# SHT31_Breakout_v1.net
KiCad netlist of a schematic drawn in EAGLE
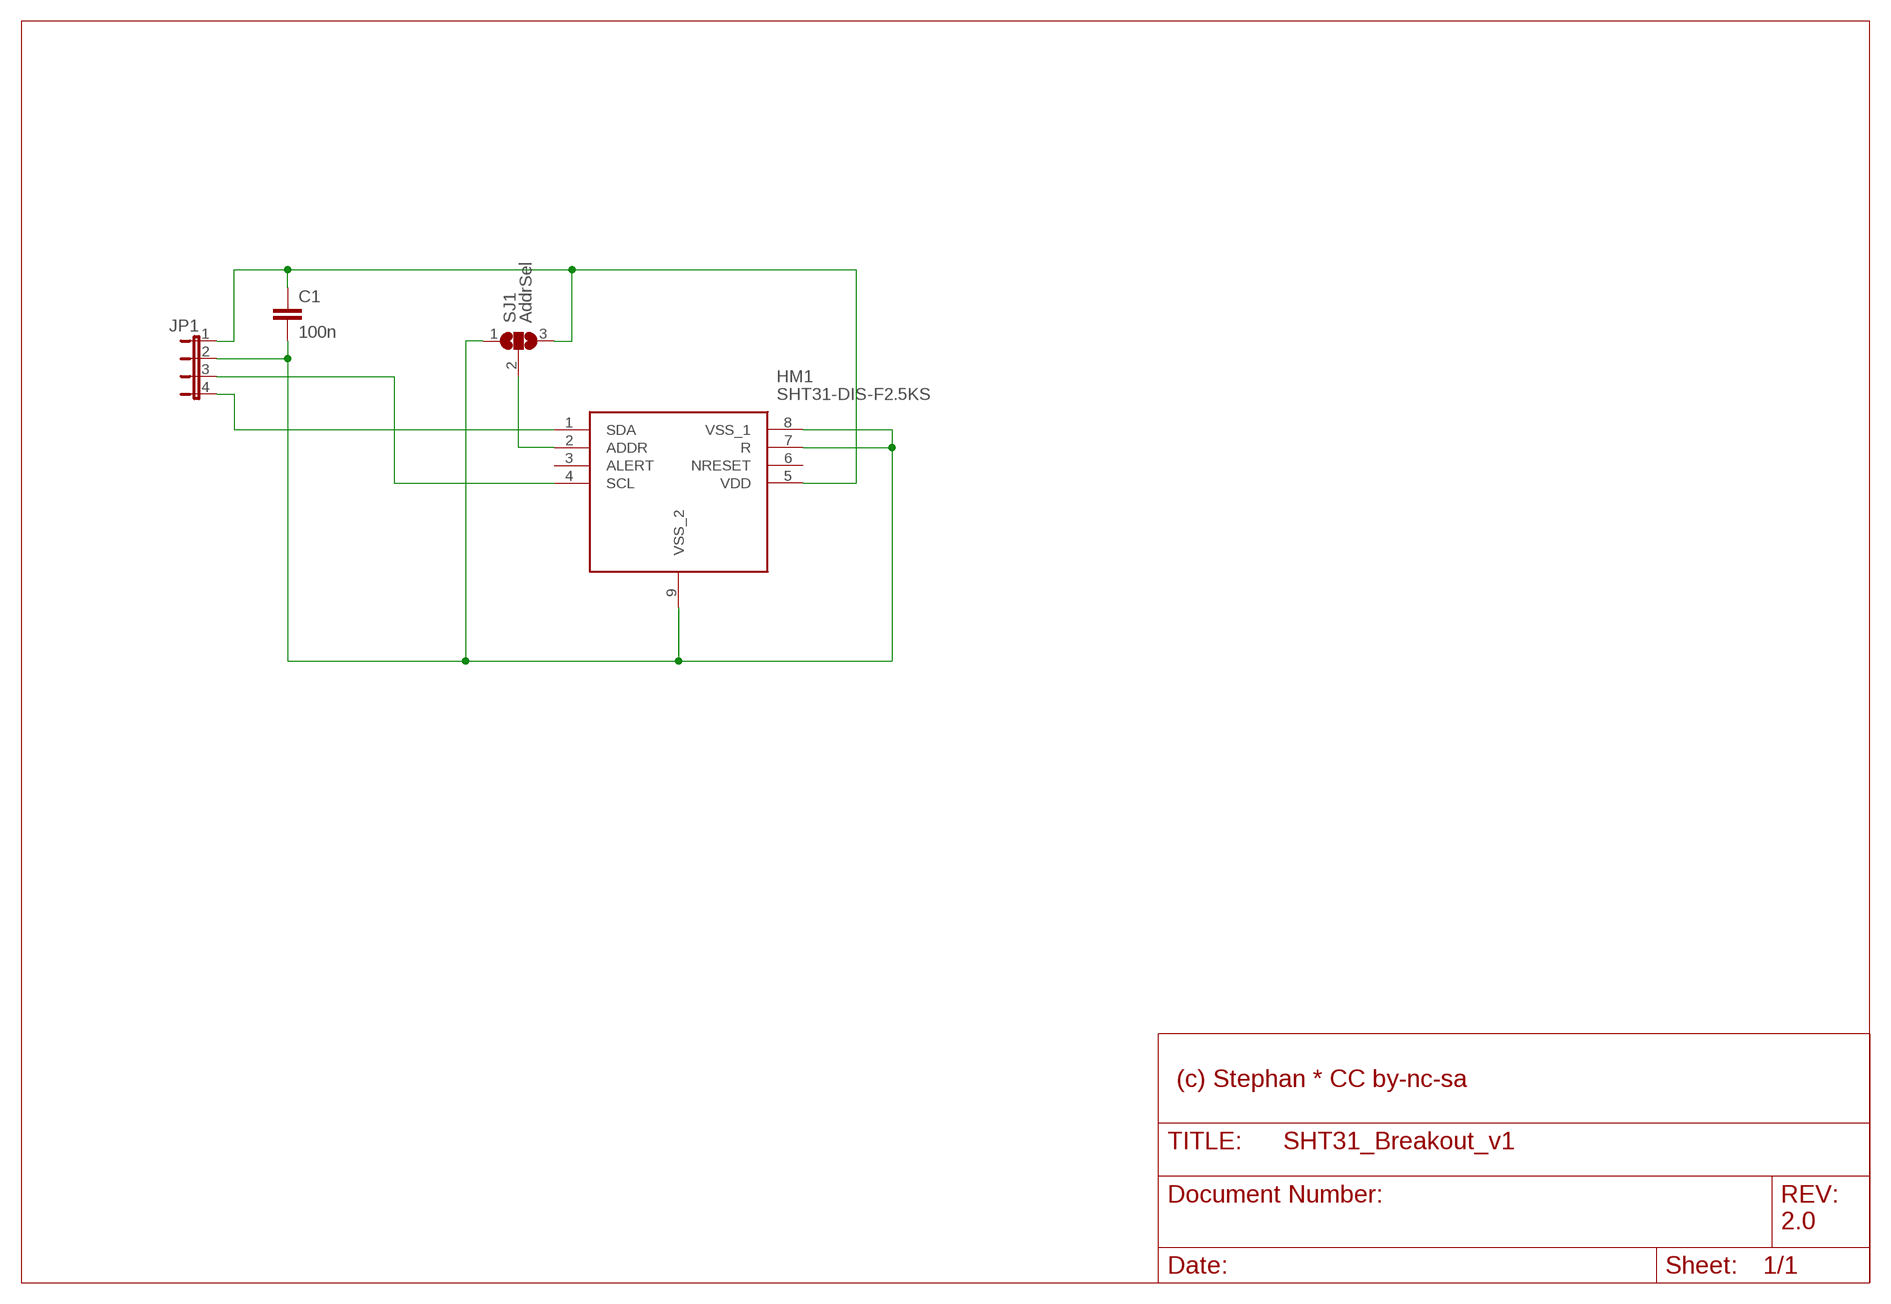
[diagram p0: schematic, sheet 1]

(export (version "E")
  (design (tool "Eeschema 10.0.6"))
  (components
    (comp (ref "C1")
      (value "100n")
      (footprint "eagle-import:C0603K")
      (libsource (lib "eagle-import") (part "C-EUC0603K"))
    )
    (comp (ref "HM1")
      (value "SHT31-DIS-F2.5KS")
      (footprint "eagle-import:SON50P250X250X90-9N")
      (fields
        (field (name "MANUFACTURER_PART_NUMBER") "SHT31-DIS-F2.5kS")
        (field (name "MOUSER_PART_NUMBER") "403-SHT31-DIS-F")
      )
      (libsource (lib "eagle-import") (part "SHT31-DIS-F2.5KS"))
    )
    (comp (ref "JP1")
      (value "JP4E")
      (footprint "eagle-import:JP4")
      (libsource (lib "eagle-import") (part "JP4E"))
    )
    (comp (ref "SJ1")
      (value "AddrSel")
      (footprint "eagle-import:SJ_2")
      (libsource (lib "eagle-import") (part "SJ2W"))
    )
  )
  (nets
    (net (code "1") (name "Net-(HM1-ADDR)") (class "Default")
      (node (ref "HM1") (pin "2") (pinfunction "ADDR_2") (pintype "input"))
      (node (ref "SJ1") (pin "2") (pinfunction "2_2") (pintype "passive"))
    )
    (net (code "2") (name "Net-(HM1-R)") (class "Default")
      (node (ref "C1") (pin "2") (pinfunction "2_2") (pintype "passive"))
      (node (ref "HM1") (pin "7") (pinfunction "R_7") (pintype "bidirectional"))
      (node (ref "HM1") (pin "8") (pinfunction "VSS_1_8") (pintype "power_in"))
      (node (ref "HM1") (pin "9") (pinfunction "VSS_2_9") (pintype "power_in"))
      (node (ref "JP1") (pin "2") (pinfunction "2_2") (pintype "passive"))
      (node (ref "SJ1") (pin "1") (pinfunction "1_1") (pintype "passive"))
    )
    (net (code "3") (name "Net-(HM1-SCL)") (class "Default")
      (node (ref "HM1") (pin "4") (pinfunction "SCL_4") (pintype "bidirectional"))
      (node (ref "JP1") (pin "3") (pinfunction "3_3") (pintype "passive"))
    )
    (net (code "4") (name "Net-(HM1-SDA)") (class "Default")
      (node (ref "HM1") (pin "1") (pinfunction "SDA_1") (pintype "bidirectional"))
      (node (ref "JP1") (pin "4") (pinfunction "4_4") (pintype "passive"))
    )
    (net (code "5") (name "Net-(HM1-VDD)") (class "Default")
      (node (ref "C1") (pin "1") (pinfunction "1_1") (pintype "passive"))
      (node (ref "HM1") (pin "5") (pinfunction "VDD_5") (pintype "power_in"))
      (node (ref "JP1") (pin "1") (pinfunction "1_1") (pintype "passive"))
      (node (ref "SJ1") (pin "3") (pinfunction "3_3") (pintype "passive"))
    )
    (net (code "6") (name "unconnected-(HM1-ALERT-Pad3)") (class "Default")
      (node (ref "HM1") (pin "3") (pinfunction "ALERT_3") (pintype "output"))
    )
    (net (code "7") (name "unconnected-(HM1-NRESET-Pad6)") (class "Default")
      (node (ref "HM1") (pin "6") (pinfunction "NRESET_6") (pintype "input"))
    )
  )
)
